# TPS5454.net
KiCad netlist of a schematic drawn in EasyEDA Pro
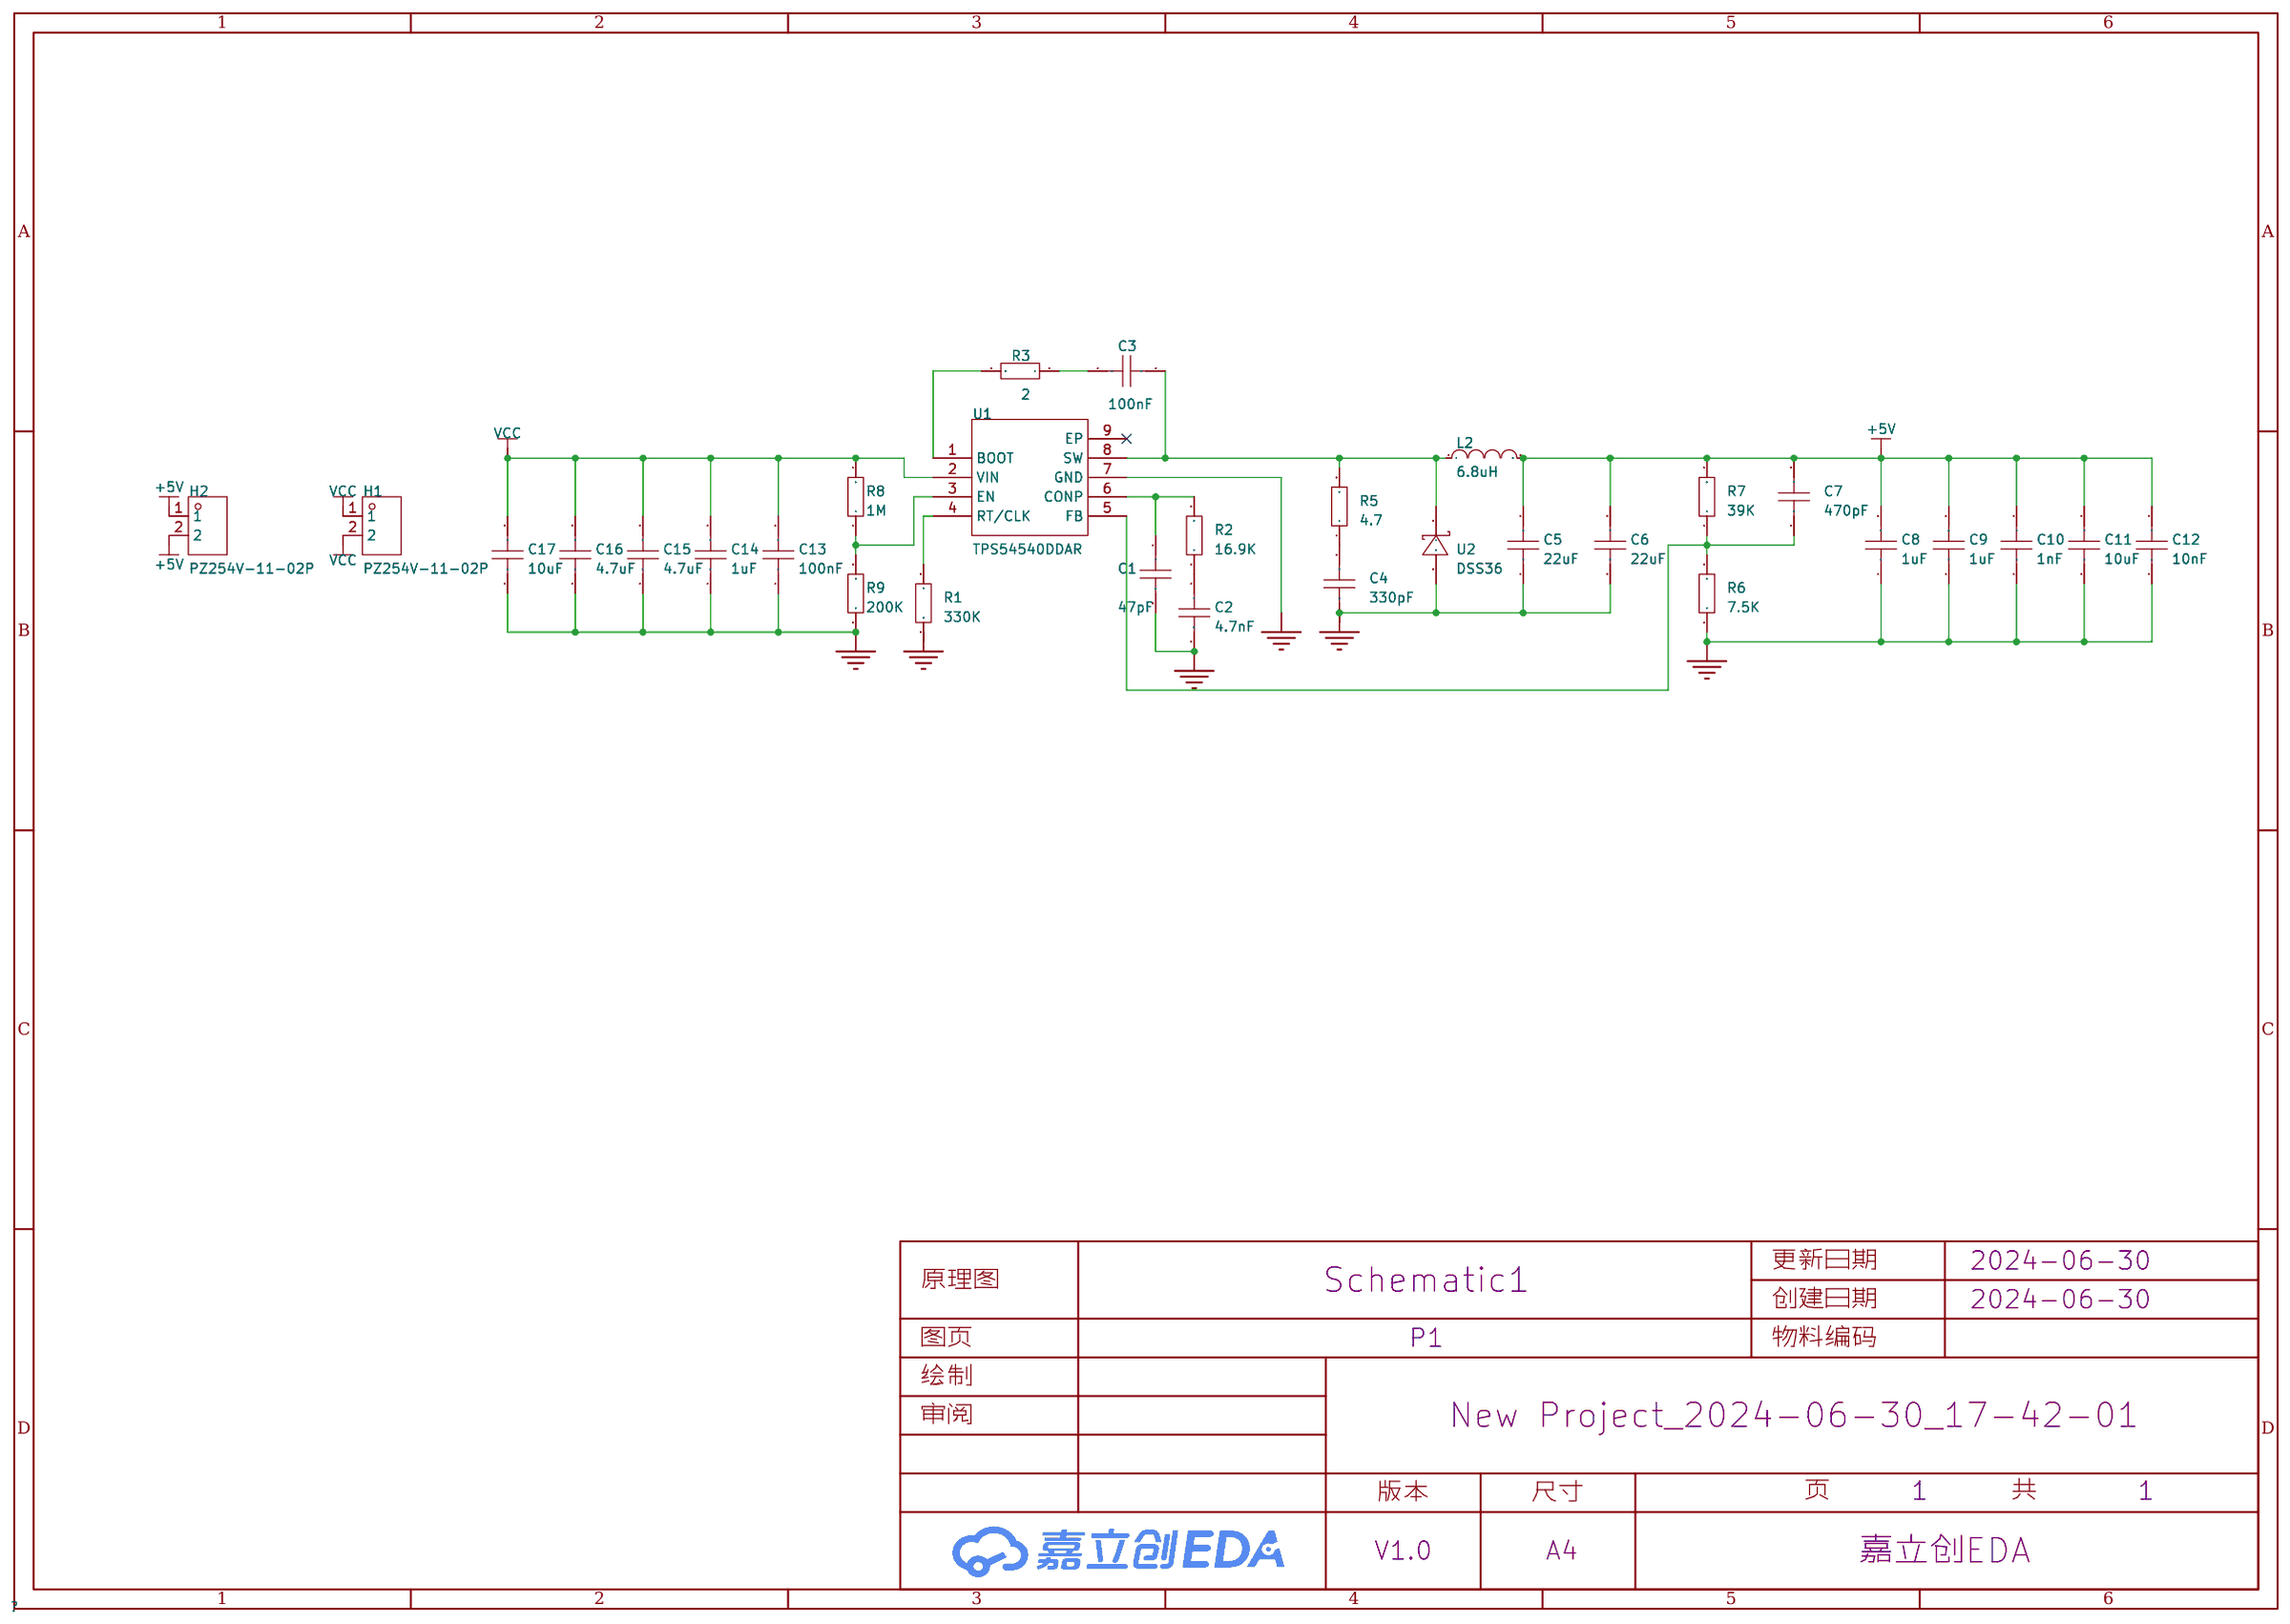
[diagram p0: schematic sheet]

(export (version "E")
  (design (tool "Eeschema 10.0.6"))
  (components
    (comp (ref "C1")
      (value "47pF")
      (footprint "easyedapro:C0603")
      (libsource (lib "easyedapro") (part "CapAcitance"))
    )
    (comp (ref "C2")
      (value "4.7nF")
      (footprint "easyedapro:C0603")
      (libsource (lib "easyedapro") (part "CapAcitance"))
    )
    (comp (ref "C3")
      (value "100nF")
      (footprint "easyedapro:C0603")
      (libsource (lib "easyedapro") (part "CapAcitance"))
    )
    (comp (ref "C4")
      (value "330pF")
      (footprint "easyedapro:C0603")
      (libsource (lib "easyedapro") (part "CapAcitance"))
    )
    (comp (ref "C5")
      (value "22uF")
      (footprint "easyedapro:C0603")
      (libsource (lib "easyedapro") (part "CapAcitance"))
    )
    (comp (ref "C6")
      (value "22uF")
      (footprint "easyedapro:C0603")
      (libsource (lib "easyedapro") (part "CapAcitance"))
    )
    (comp (ref "C7")
      (value "470pF")
      (footprint "easyedapro:C0603")
      (libsource (lib "easyedapro") (part "CapAcitance"))
    )
    (comp (ref "C8")
      (value "1uF")
      (footprint "easyedapro:C0603")
      (libsource (lib "easyedapro") (part "CapAcitance"))
    )
    (comp (ref "C9")
      (value "1uF")
      (footprint "easyedapro:C0603")
      (libsource (lib "easyedapro") (part "CapAcitance"))
    )
    (comp (ref "C10")
      (value "1nF")
      (footprint "easyedapro:C0603")
      (libsource (lib "easyedapro") (part "CapAcitance"))
    )
    (comp (ref "C11")
      (value "10uF")
      (footprint "easyedapro:C0603")
      (libsource (lib "easyedapro") (part "CapAcitance"))
    )
    (comp (ref "C12")
      (value "10nF")
      (footprint "easyedapro:C0603")
      (libsource (lib "easyedapro") (part "CapAcitance"))
    )
    (comp (ref "C13")
      (value "100nF")
      (footprint "easyedapro:C0603")
      (libsource (lib "easyedapro") (part "CapAcitance"))
    )
    (comp (ref "C14")
      (value "1uF")
      (footprint "easyedapro:C0603")
      (libsource (lib "easyedapro") (part "CapAcitance"))
    )
    (comp (ref "C15")
      (value "4.7uF")
      (footprint "easyedapro:C0603")
      (libsource (lib "easyedapro") (part "CapAcitance"))
    )
    (comp (ref "C16")
      (value "4.7uF")
      (footprint "easyedapro:C0603")
      (libsource (lib "easyedapro") (part "CapAcitance"))
    )
    (comp (ref "C17")
      (value "10uF")
      (footprint "easyedapro:C0603")
      (libsource (lib "easyedapro") (part "CapAcitance"))
    )
    (comp (ref "H1")
      (value "PZ254V-11-02P")
      (footprint "easyedapro:HDR-TH_2P-P2.54-V-M")
      (fields (field (name "Manufacturer") "XFCN(兴飞)"))
      (libsource (lib "easyedapro") (part "PZ254V-11-02P"))
    )
    (comp (ref "H2")
      (value "PZ254V-11-02P")
      (footprint "easyedapro:HDR-TH_2P-P2.54-V-M")
      (fields (field (name "Manufacturer") "XFCN(兴飞)"))
      (libsource (lib "easyedapro") (part "PZ254V-11-02P"))
    )
    (comp (ref "L2")
      (value "6.8uH")
      (footprint "easyedapro:IND-SMD_L7.0-W6.6")
      (description "电感值:6.8uH;精度:±20%;额定电流:5A;饱和电流(Isat):6A;类型:一体成型电感;")
      (fields (field (name "Manufacturer Part") "FXL0630-6R8-M") (field (name "Manufacturer") "cjiang(长江微电)"))
      (libsource (lib "easyedapro") (part "FXL0630-6R8-M"))
    )
    (comp (ref "R1") (value "330K") (footprint "easyedapro:R0603") (libsource (lib "easyedapro") (part "电阻")))
    (comp (ref "R2")
      (value "16.9K")
      (footprint "easyedapro:R0603")
      (libsource (lib "easyedapro") (part "电阻"))
    )
    (comp (ref "R3") (value "2") (footprint "easyedapro:R0603") (libsource (lib "easyedapro") (part "电阻")))
    (comp (ref "R5") (value "4.7") (footprint "easyedapro:R0603") (libsource (lib "easyedapro") (part "电阻")))
    (comp (ref "R6") (value "7.5K") (footprint "easyedapro:R0603") (libsource (lib "easyedapro") (part "电阻")))
    (comp (ref "R7") (value "39K") (footprint "easyedapro:R0603") (libsource (lib "easyedapro") (part "电阻")))
    (comp (ref "R8") (value "1M") (footprint "easyedapro:R0603") (libsource (lib "easyedapro") (part "电阻")))
    (comp (ref "R9") (value "200K") (footprint "easyedapro:R0603") (libsource (lib "easyedapro") (part "电阻")))
    (comp (ref "U1")
      (value "TPS54540DDAR")
      (footprint "easyedapro:SOIC-8_L4.9-W3.9-P1.27-LS6.0-BL-EP")
      (description "功能类型:降压型;输出类型:可调;输入电压:4.5V~42V;输出电压:800mV~41.1V;输出电流(最大值):5A;")
      (fields (field (name "Manufacturer") "TI(德州仪器)"))
      (libsource (lib "easyedapro") (part "TPS54540DDAR"))
    )
    (comp (ref "U2")
      (value "DSS36")
      (footprint "easyedapro:SOD-123FL_L2.6-W1.6-LS3.6-RD")
      (fields (field (name "Manufacturer") "CJ(江苏长电/长晶)"))
      (libsource (lib "easyedapro") (part "DSS36"))
    )
  )
  (nets
    (net (code "1") (name "+5V") (class "Default")
      (node (ref "C10") (pin "2") (pinfunction "2_2") (pintype "input"))
      (node (ref "C11") (pin "2") (pinfunction "2_2") (pintype "input"))
      (node (ref "C12") (pin "2") (pinfunction "2_2") (pintype "input"))
      (node (ref "C5") (pin "2") (pinfunction "2_2") (pintype "input"))
      (node (ref "C6") (pin "2") (pinfunction "2_2") (pintype "input"))
      (node (ref "C7") (pin "2") (pinfunction "2_2") (pintype "input"))
      (node (ref "C8") (pin "2") (pinfunction "2_2") (pintype "input"))
      (node (ref "C9") (pin "2") (pinfunction "2_2") (pintype "input"))
      (node (ref "H2") (pin "1") (pinfunction "1_1") (pintype "unspecified"))
      (node (ref "H2") (pin "2") (pinfunction "2_2") (pintype "unspecified"))
      (node (ref "L2") (pin "2") (pinfunction "2_2") (pintype "unspecified"))
      (node (ref "R7") (pin "2") (pinfunction "2_2") (pintype "input"))
    )
    (net (code "2") (name "GND") (class "Default")
      (node (ref "C1") (pin "2") (pinfunction "2_2") (pintype "input"))
      (node (ref "C10") (pin "1") (pinfunction "1_1") (pintype "input"))
      (node (ref "C11") (pin "1") (pinfunction "1_1") (pintype "input"))
      (node (ref "C12") (pin "1") (pinfunction "1_1") (pintype "input"))
      (node (ref "C13") (pin "1") (pinfunction "1_1") (pintype "input"))
      (node (ref "C14") (pin "1") (pinfunction "1_1") (pintype "input"))
      (node (ref "C15") (pin "1") (pinfunction "1_1") (pintype "input"))
      (node (ref "C16") (pin "1") (pinfunction "1_1") (pintype "input"))
      (node (ref "C17") (pin "1") (pinfunction "1_1") (pintype "input"))
      (node (ref "C2") (pin "2") (pinfunction "2_2") (pintype "input"))
      (node (ref "C4") (pin "1") (pinfunction "1_1") (pintype "input"))
      (node (ref "C5") (pin "1") (pinfunction "1_1") (pintype "input"))
      (node (ref "C6") (pin "1") (pinfunction "1_1") (pintype "input"))
      (node (ref "C8") (pin "1") (pinfunction "1_1") (pintype "input"))
      (node (ref "C9") (pin "1") (pinfunction "1_1") (pintype "input"))
      (node (ref "R1") (pin "1") (pinfunction "1_1") (pintype "input"))
      (node (ref "R6") (pin "1") (pinfunction "1_1") (pintype "input"))
      (node (ref "R9") (pin "1") (pinfunction "1_1") (pintype "input"))
      (node (ref "U1") (pin "7") (pinfunction "GND_7") (pintype "unspecified"))
      (node (ref "U2") (pin "2") (pinfunction "A_2") (pintype "input"))
    )
    (net (code "3") (name "Net-(C2-Pad1)") (class "Default")
      (node (ref "C2") (pin "1") (pinfunction "1_1") (pintype "input"))
      (node (ref "R2") (pin "1") (pinfunction "1_1") (pintype "input"))
    )
    (net (code "4") (name "Net-(C3-Pad1)") (class "Default")
      (node (ref "C3") (pin "1") (pinfunction "1_1") (pintype "input"))
      (node (ref "R3") (pin "1") (pinfunction "1_1") (pintype "input"))
    )
    (net (code "5") (name "Net-(C4-Pad2)") (class "Default")
      (node (ref "C4") (pin "2") (pinfunction "2_2") (pintype "input"))
      (node (ref "R5") (pin "1") (pinfunction "1_1") (pintype "input"))
    )
    (net (code "6") (name "Net-(U1-BOOT)") (class "Default")
      (node (ref "R3") (pin "2") (pinfunction "2_2") (pintype "input"))
      (node (ref "U1") (pin "1") (pinfunction "BOOT_1") (pintype "unspecified"))
    )
    (net (code "7") (name "Net-(U1-CONP)") (class "Default")
      (node (ref "C1") (pin "1") (pinfunction "1_1") (pintype "input"))
      (node (ref "R2") (pin "2") (pinfunction "2_2") (pintype "input"))
      (node (ref "U1") (pin "6") (pinfunction "CONP_6") (pintype "unspecified"))
    )
    (net (code "8") (name "Net-(U1-EN)") (class "Default")
      (node (ref "R8") (pin "1") (pinfunction "1_1") (pintype "input"))
      (node (ref "R9") (pin "2") (pinfunction "2_2") (pintype "input"))
      (node (ref "U1") (pin "3") (pinfunction "EN_3") (pintype "unspecified"))
    )
    (net (code "9") (name "Net-(U1-FB)") (class "Default")
      (node (ref "C7") (pin "1") (pinfunction "1_1") (pintype "input"))
      (node (ref "R6") (pin "2") (pinfunction "2_2") (pintype "input"))
      (node (ref "R7") (pin "1") (pinfunction "1_1") (pintype "input"))
      (node (ref "U1") (pin "5") (pinfunction "FB_5") (pintype "unspecified"))
    )
    (net (code "10") (name "Net-(U1-RT{slash}CLK)") (class "Default")
      (node (ref "R1") (pin "2") (pinfunction "2_2") (pintype "input"))
      (node (ref "U1") (pin "4") (pinfunction "RT/CLK_4") (pintype "unspecified"))
    )
    (net (code "11") (name "Net-(U1-SW)") (class "Default")
      (node (ref "C3") (pin "2") (pinfunction "2_2") (pintype "input"))
      (node (ref "L2") (pin "1") (pinfunction "1_1") (pintype "unspecified"))
      (node (ref "R5") (pin "2") (pinfunction "2_2") (pintype "input"))
      (node (ref "U1") (pin "8") (pinfunction "SW_8") (pintype "unspecified"))
      (node (ref "U2") (pin "1") (pinfunction "K_1") (pintype "input"))
    )
    (net (code "12") (name "VCC") (class "Default")
      (node (ref "C13") (pin "2") (pinfunction "2_2") (pintype "input"))
      (node (ref "C14") (pin "2") (pinfunction "2_2") (pintype "input"))
      (node (ref "C15") (pin "2") (pinfunction "2_2") (pintype "input"))
      (node (ref "C16") (pin "2") (pinfunction "2_2") (pintype "input"))
      (node (ref "C17") (pin "2") (pinfunction "2_2") (pintype "input"))
      (node (ref "H1") (pin "1") (pinfunction "1_1") (pintype "unspecified"))
      (node (ref "H1") (pin "2") (pinfunction "2_2") (pintype "unspecified"))
      (node (ref "R8") (pin "2") (pinfunction "2_2") (pintype "input"))
      (node (ref "U1") (pin "2") (pinfunction "VIN_2") (pintype "unspecified"))
    )
    (net (code "13") (name "unconnected-(U1-EP-Pad9)") (class "Default")
      (node (ref "U1") (pin "9") (pinfunction "EP_9") (pintype "unspecified+no_connect"))
    )
  )
)
